# ADC_CPU.net
KiCad netlist of a schematic drawn in Altium Designer
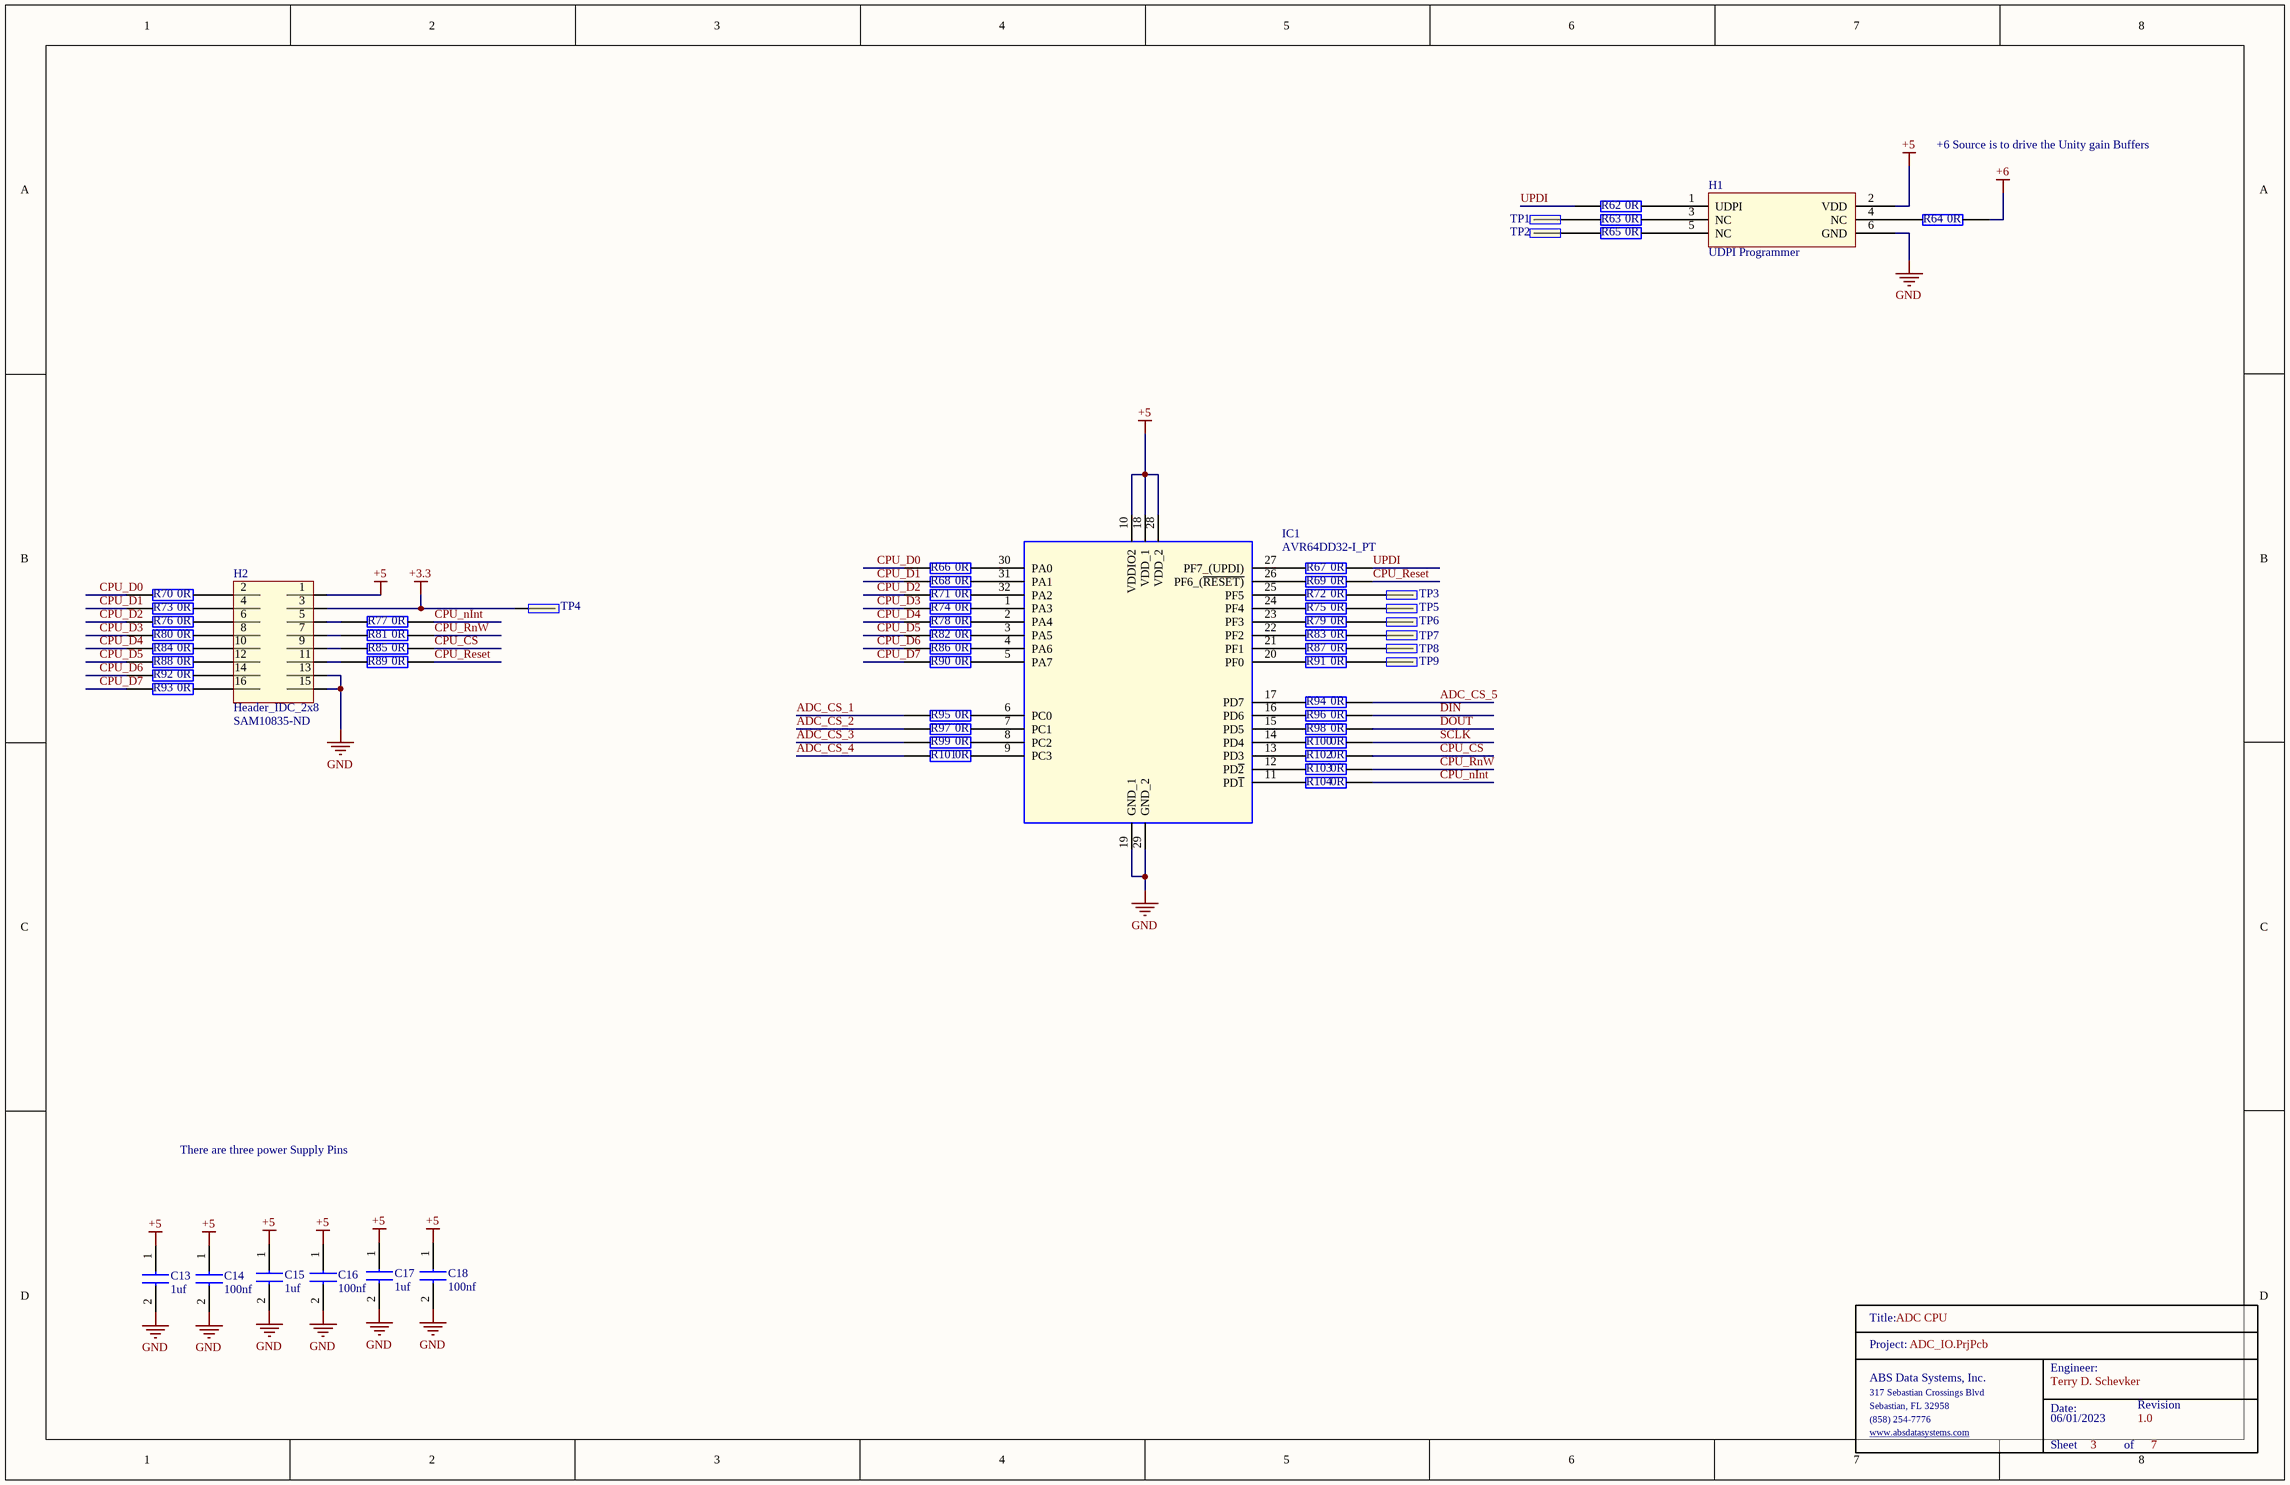
[diagram p0: ADC_CPU.SchDoc]

(export (version "E")
  (design (tool "Eeschema 10.0.6"))
  (components
    (comp (ref "C13")
      (value "1uf")
      (footprint "0603")
      (description "Samsung Electro-Mechanics 0603 1uf")
      (libsource (lib "Capacitors") (part "CL10B105KA8NNNL"))
    )
    (comp (ref "C14")
      (value "100nf")
      (footprint "0603")
      (description "Samsung Electro-Mechanics 0603 100nf")
      (libsource (lib "Capacitors") (part "CL10B104JB8NNNC"))
    )
    (comp (ref "C15")
      (value "1uf")
      (footprint "0603")
      (description "Samsung Electro-Mechanics 0603 1uf")
      (libsource (lib "Capacitors") (part "CL10B105KA8NNNL"))
    )
    (comp (ref "C16")
      (value "100nf")
      (footprint "0603")
      (description "Samsung Electro-Mechanics 0603 100nf")
      (libsource (lib "Capacitors") (part "CL10B104JB8NNNC"))
    )
    (comp (ref "C17")
      (value "1uf")
      (footprint "0603")
      (description "Samsung Electro-Mechanics 0603 1uf")
      (libsource (lib "Capacitors") (part "CL10B105KA8NNNL"))
    )
    (comp (ref "C18")
      (value "100nf")
      (footprint "0603")
      (description "Samsung Electro-Mechanics 0603 100nf")
      (libsource (lib "Capacitors") (part "CL10B104JB8NNNC"))
    )
    (comp (ref "H1")
      (value "UDPI Programmer")
      (footprint "HDR2X3")
      (description "6 Pin 2X3 Through Hole Header")
      (libsource (lib "Misc") (part "UDPI Programmer"))
    )
    (comp (ref "H2")
      (value "Header_IDC_2x8")
      (footprint "HEADER16")
      (description "16 Pin 2x8 Through Hold IDC Connector")
      (fields
        (field (name "MANUFACTURER") "Samtec")
        (field (name "MANUFACTURER PART NUMBER") "TST-108-01-G-D")
        (field (name "SUPPLIER PART NUMBER 1") "SAM10835-ND")
      )
      (libsource (lib "Misc") (part "Header_IDC_2x8"))
    )
    (comp (ref "IC1")
      (value "AVR64DD32-I_PT")
      (footprint "CPU_Memory:QFP80P900X900X120-32N")
      (description "Integrated Circuit")
      (fields (field (name "MANUFACTURER_PART_NUMBER") "AVR64DD32-I/PT ¦ MULTI-VOLTAGE I/O"))
      (libsource (lib "CPU_Memory") (part "AVR64DD32-I_PT"))
    )
    (comp (ref "R62")
      (value "0R")
      (footprint "0603")
      (description "YAGEO 0603 0 ohm")
      (fields
        (field (name "MOUSER PART NUMBER") "603-RC0603JR-070RL")
        (field (name "MANUFACTURER_PART_NUMBER") "RC0603JR-070RL")
      )
      (libsource (lib "Resistors") (part "RC0603JR-070RL"))
    )
    (comp (ref "R63")
      (value "0R")
      (footprint "0603")
      (description "YAGEO 0603 0 ohm")
      (fields
        (field (name "MOUSER PART NUMBER") "603-RC0603JR-070RL")
        (field (name "MANUFACTURER_PART_NUMBER") "RC0603JR-070RL")
      )
      (libsource (lib "Resistors") (part "RC0603JR-070RL"))
    )
    (comp (ref "R64")
      (value "0R")
      (footprint "0603")
      (description "YAGEO 0603 0 ohm")
      (fields
        (field (name "MOUSER PART NUMBER") "603-RC0603JR-070RL")
        (field (name "MANUFACTURER_PART_NUMBER") "RC0603JR-070RL")
      )
      (libsource (lib "Resistors") (part "RC0603JR-070RL"))
    )
    (comp (ref "R65")
      (value "0R")
      (footprint "0603")
      (description "YAGEO 0603 0 ohm")
      (fields
        (field (name "MOUSER PART NUMBER") "603-RC0603JR-070RL")
        (field (name "MANUFACTURER_PART_NUMBER") "RC0603JR-070RL")
      )
      (libsource (lib "Resistors") (part "RC0603JR-070RL"))
    )
    (comp (ref "R66")
      (value "0R")
      (footprint "0603")
      (description "YAGEO 0603 0 ohm")
      (fields
        (field (name "MOUSER PART NUMBER") "603-RC0603JR-070RL")
        (field (name "MANUFACTURER_PART_NUMBER") "RC0603JR-070RL")
      )
      (libsource (lib "Resistors") (part "RC0603JR-070RL"))
    )
    (comp (ref "R67")
      (value "0R")
      (footprint "0603")
      (description "YAGEO 0603 0 ohm")
      (fields
        (field (name "MOUSER PART NUMBER") "603-RC0603JR-070RL")
        (field (name "MANUFACTURER_PART_NUMBER") "RC0603JR-070RL")
      )
      (libsource (lib "Resistors") (part "RC0603JR-070RL"))
    )
    (comp (ref "R68")
      (value "0R")
      (footprint "0603")
      (description "YAGEO 0603 0 ohm")
      (fields
        (field (name "MOUSER PART NUMBER") "603-RC0603JR-070RL")
        (field (name "MANUFACTURER_PART_NUMBER") "RC0603JR-070RL")
      )
      (libsource (lib "Resistors") (part "RC0603JR-070RL"))
    )
    (comp (ref "R69")
      (value "0R")
      (footprint "0603")
      (description "YAGEO 0603 0 ohm")
      (fields
        (field (name "MOUSER PART NUMBER") "603-RC0603JR-070RL")
        (field (name "MANUFACTURER_PART_NUMBER") "RC0603JR-070RL")
      )
      (libsource (lib "Resistors") (part "RC0603JR-070RL"))
    )
    (comp (ref "R70")
      (value "0R")
      (footprint "0603")
      (description "YAGEO 0603 0 ohm")
      (fields
        (field (name "MOUSER PART NUMBER") "603-RC0603JR-070RL")
        (field (name "MANUFACTURER_PART_NUMBER") "RC0603JR-070RL")
      )
      (libsource (lib "Resistors") (part "RC0603JR-070RL"))
    )
    (comp (ref "R71")
      (value "0R")
      (footprint "0603")
      (description "YAGEO 0603 0 ohm")
      (fields
        (field (name "MOUSER PART NUMBER") "603-RC0603JR-070RL")
        (field (name "MANUFACTURER_PART_NUMBER") "RC0603JR-070RL")
      )
      (libsource (lib "Resistors") (part "RC0603JR-070RL"))
    )
    (comp (ref "R72")
      (value "0R")
      (footprint "0603")
      (description "YAGEO 0603 0 ohm")
      (fields
        (field (name "MOUSER PART NUMBER") "603-RC0603JR-070RL")
        (field (name "MANUFACTURER_PART_NUMBER") "RC0603JR-070RL")
      )
      (libsource (lib "Resistors") (part "RC0603JR-070RL"))
    )
    (comp (ref "R73")
      (value "0R")
      (footprint "0603")
      (description "YAGEO 0603 0 ohm")
      (fields
        (field (name "MOUSER PART NUMBER") "603-RC0603JR-070RL")
        (field (name "MANUFACTURER_PART_NUMBER") "RC0603JR-070RL")
      )
      (libsource (lib "Resistors") (part "RC0603JR-070RL"))
    )
    (comp (ref "R74")
      (value "0R")
      (footprint "0603")
      (description "YAGEO 0603 0 ohm")
      (fields
        (field (name "MOUSER PART NUMBER") "603-RC0603JR-070RL")
        (field (name "MANUFACTURER_PART_NUMBER") "RC0603JR-070RL")
      )
      (libsource (lib "Resistors") (part "RC0603JR-070RL"))
    )
    (comp (ref "R75")
      (value "0R")
      (footprint "0603")
      (description "YAGEO 0603 0 ohm")
      (fields
        (field (name "MOUSER PART NUMBER") "603-RC0603JR-070RL")
        (field (name "MANUFACTURER_PART_NUMBER") "RC0603JR-070RL")
      )
      (libsource (lib "Resistors") (part "RC0603JR-070RL"))
    )
    (comp (ref "R76")
      (value "0R")
      (footprint "0603")
      (description "YAGEO 0603 0 ohm")
      (fields
        (field (name "MOUSER PART NUMBER") "603-RC0603JR-070RL")
        (field (name "MANUFACTURER_PART_NUMBER") "RC0603JR-070RL")
      )
      (libsource (lib "Resistors") (part "RC0603JR-070RL"))
    )
    (comp (ref "R77")
      (value "0R")
      (footprint "0603")
      (description "YAGEO 0603 0 ohm")
      (fields
        (field (name "MOUSER PART NUMBER") "603-RC0603JR-070RL")
        (field (name "MANUFACTURER_PART_NUMBER") "RC0603JR-070RL")
      )
      (libsource (lib "Resistors") (part "RC0603JR-070RL"))
    )
    (comp (ref "R78")
      (value "0R")
      (footprint "0603")
      (description "YAGEO 0603 0 ohm")
      (fields
        (field (name "MOUSER PART NUMBER") "603-RC0603JR-070RL")
        (field (name "MANUFACTURER_PART_NUMBER") "RC0603JR-070RL")
      )
      (libsource (lib "Resistors") (part "RC0603JR-070RL"))
    )
    (comp (ref "R79")
      (value "0R")
      (footprint "0603")
      (description "YAGEO 0603 0 ohm")
      (fields
        (field (name "MOUSER PART NUMBER") "603-RC0603JR-070RL")
        (field (name "MANUFACTURER_PART_NUMBER") "RC0603JR-070RL")
      )
      (libsource (lib "Resistors") (part "RC0603JR-070RL"))
    )
    (comp (ref "R80")
      (value "0R")
      (footprint "0603")
      (description "YAGEO 0603 0 ohm")
      (fields
        (field (name "MOUSER PART NUMBER") "603-RC0603JR-070RL")
        (field (name "MANUFACTURER_PART_NUMBER") "RC0603JR-070RL")
      )
      (libsource (lib "Resistors") (part "RC0603JR-070RL"))
    )
    (comp (ref "R81")
      (value "0R")
      (footprint "0603")
      (description "YAGEO 0603 0 ohm")
      (fields
        (field (name "MOUSER PART NUMBER") "603-RC0603JR-070RL")
        (field (name "MANUFACTURER_PART_NUMBER") "RC0603JR-070RL")
      )
      (libsource (lib "Resistors") (part "RC0603JR-070RL"))
    )
    (comp (ref "R82")
      (value "0R")
      (footprint "0603")
      (description "YAGEO 0603 0 ohm")
      (fields
        (field (name "MOUSER PART NUMBER") "603-RC0603JR-070RL")
        (field (name "MANUFACTURER_PART_NUMBER") "RC0603JR-070RL")
      )
      (libsource (lib "Resistors") (part "RC0603JR-070RL"))
    )
    (comp (ref "R83")
      (value "0R")
      (footprint "0603")
      (description "YAGEO 0603 0 ohm")
      (fields
        (field (name "MOUSER PART NUMBER") "603-RC0603JR-070RL")
        (field (name "MANUFACTURER_PART_NUMBER") "RC0603JR-070RL")
      )
      (libsource (lib "Resistors") (part "RC0603JR-070RL"))
    )
    (comp (ref "R84")
      (value "0R")
      (footprint "0603")
      (description "YAGEO 0603 0 ohm")
      (fields
        (field (name "MOUSER PART NUMBER") "603-RC0603JR-070RL")
        (field (name "MANUFACTURER_PART_NUMBER") "RC0603JR-070RL")
      )
      (libsource (lib "Resistors") (part "RC0603JR-070RL"))
    )
    (comp (ref "R85")
      (value "0R")
      (footprint "0603")
      (description "YAGEO 0603 0 ohm")
      (fields
        (field (name "MOUSER PART NUMBER") "603-RC0603JR-070RL")
        (field (name "MANUFACTURER_PART_NUMBER") "RC0603JR-070RL")
      )
      (libsource (lib "Resistors") (part "RC0603JR-070RL"))
    )
    (comp (ref "R86")
      (value "0R")
      (footprint "0603")
      (description "YAGEO 0603 0 ohm")
      (fields
        (field (name "MOUSER PART NUMBER") "603-RC0603JR-070RL")
        (field (name "MANUFACTURER_PART_NUMBER") "RC0603JR-070RL")
      )
      (libsource (lib "Resistors") (part "RC0603JR-070RL"))
    )
    (comp (ref "R87")
      (value "0R")
      (footprint "0603")
      (description "YAGEO 0603 0 ohm")
      (fields
        (field (name "MOUSER PART NUMBER") "603-RC0603JR-070RL")
        (field (name "MANUFACTURER_PART_NUMBER") "RC0603JR-070RL")
      )
      (libsource (lib "Resistors") (part "RC0603JR-070RL"))
    )
    (comp (ref "R88")
      (value "0R")
      (footprint "0603")
      (description "YAGEO 0603 0 ohm")
      (fields
        (field (name "MOUSER PART NUMBER") "603-RC0603JR-070RL")
        (field (name "MANUFACTURER_PART_NUMBER") "RC0603JR-070RL")
      )
      (libsource (lib "Resistors") (part "RC0603JR-070RL"))
    )
    (comp (ref "R89")
      (value "0R")
      (footprint "0603")
      (description "YAGEO 0603 0 ohm")
      (fields
        (field (name "MOUSER PART NUMBER") "603-RC0603JR-070RL")
        (field (name "MANUFACTURER_PART_NUMBER") "RC0603JR-070RL")
      )
      (libsource (lib "Resistors") (part "RC0603JR-070RL"))
    )
    (comp (ref "R90")
      (value "0R")
      (footprint "0603")
      (description "YAGEO 0603 0 ohm")
      (fields
        (field (name "MOUSER PART NUMBER") "603-RC0603JR-070RL")
        (field (name "MANUFACTURER_PART_NUMBER") "RC0603JR-070RL")
      )
      (libsource (lib "Resistors") (part "RC0603JR-070RL"))
    )
    (comp (ref "R91")
      (value "0R")
      (footprint "0603")
      (description "YAGEO 0603 0 ohm")
      (fields
        (field (name "MOUSER PART NUMBER") "603-RC0603JR-070RL")
        (field (name "MANUFACTURER_PART_NUMBER") "RC0603JR-070RL")
      )
      (libsource (lib "Resistors") (part "RC0603JR-070RL"))
    )
    (comp (ref "R92")
      (value "0R")
      (footprint "0603")
      (description "YAGEO 0603 0 ohm")
      (fields
        (field (name "MOUSER PART NUMBER") "603-RC0603JR-070RL")
        (field (name "MANUFACTURER_PART_NUMBER") "RC0603JR-070RL")
      )
      (libsource (lib "Resistors") (part "RC0603JR-070RL"))
    )
    (comp (ref "R93")
      (value "0R")
      (footprint "0603")
      (description "YAGEO 0603 0 ohm")
      (fields
        (field (name "MOUSER PART NUMBER") "603-RC0603JR-070RL")
        (field (name "MANUFACTURER_PART_NUMBER") "RC0603JR-070RL")
      )
      (libsource (lib "Resistors") (part "RC0603JR-070RL"))
    )
    (comp (ref "R94")
      (value "0R")
      (footprint "0603")
      (description "YAGEO 0603 0 ohm")
      (fields
        (field (name "MOUSER PART NUMBER") "603-RC0603JR-070RL")
        (field (name "MANUFACTURER_PART_NUMBER") "RC0603JR-070RL")
      )
      (libsource (lib "Resistors") (part "RC0603JR-070RL"))
    )
    (comp (ref "R95")
      (value "0R")
      (footprint "0603")
      (description "YAGEO 0603 0 ohm")
      (fields
        (field (name "MOUSER PART NUMBER") "603-RC0603JR-070RL")
        (field (name "MANUFACTURER_PART_NUMBER") "RC0603JR-070RL")
      )
      (libsource (lib "Resistors") (part "RC0603JR-070RL"))
    )
    (comp (ref "R96")
      (value "0R")
      (footprint "0603")
      (description "YAGEO 0603 0 ohm")
      (fields
        (field (name "MOUSER PART NUMBER") "603-RC0603JR-070RL")
        (field (name "MANUFACTURER_PART_NUMBER") "RC0603JR-070RL")
      )
      (libsource (lib "Resistors") (part "RC0603JR-070RL"))
    )
    (comp (ref "R97")
      (value "0R")
      (footprint "0603")
      (description "YAGEO 0603 0 ohm")
      (fields
        (field (name "MOUSER PART NUMBER") "603-RC0603JR-070RL")
        (field (name "MANUFACTURER_PART_NUMBER") "RC0603JR-070RL")
      )
      (libsource (lib "Resistors") (part "RC0603JR-070RL"))
    )
    (comp (ref "R98")
      (value "0R")
      (footprint "0603")
      (description "YAGEO 0603 0 ohm")
      (fields
        (field (name "MOUSER PART NUMBER") "603-RC0603JR-070RL")
        (field (name "MANUFACTURER_PART_NUMBER") "RC0603JR-070RL")
      )
      (libsource (lib "Resistors") (part "RC0603JR-070RL"))
    )
    (comp (ref "R99")
      (value "0R")
      (footprint "0603")
      (description "YAGEO 0603 0 ohm")
      (fields
        (field (name "MOUSER PART NUMBER") "603-RC0603JR-070RL")
        (field (name "MANUFACTURER_PART_NUMBER") "RC0603JR-070RL")
      )
      (libsource (lib "Resistors") (part "RC0603JR-070RL"))
    )
    (comp (ref "R100")
      (value "0R")
      (footprint "0603")
      (description "YAGEO 0603 0 ohm")
      (fields
        (field (name "MOUSER PART NUMBER") "603-RC0603JR-070RL")
        (field (name "MANUFACTURER_PART_NUMBER") "RC0603JR-070RL")
      )
      (libsource (lib "Resistors") (part "RC0603JR-070RL"))
    )
    (comp (ref "R101")
      (value "0R")
      (footprint "0603")
      (description "YAGEO 0603 0 ohm")
      (fields
        (field (name "MOUSER PART NUMBER") "603-RC0603JR-070RL")
        (field (name "MANUFACTURER_PART_NUMBER") "RC0603JR-070RL")
      )
      (libsource (lib "Resistors") (part "RC0603JR-070RL"))
    )
    (comp (ref "R102")
      (value "0R")
      (footprint "0603")
      (description "YAGEO 0603 0 ohm")
      (fields
        (field (name "MOUSER PART NUMBER") "603-RC0603JR-070RL")
        (field (name "MANUFACTURER_PART_NUMBER") "RC0603JR-070RL")
      )
      (libsource (lib "Resistors") (part "RC0603JR-070RL"))
    )
    (comp (ref "R103")
      (value "0R")
      (footprint "0603")
      (description "YAGEO 0603 0 ohm")
      (fields
        (field (name "MOUSER PART NUMBER") "603-RC0603JR-070RL")
        (field (name "MANUFACTURER_PART_NUMBER") "RC0603JR-070RL")
      )
      (libsource (lib "Resistors") (part "RC0603JR-070RL"))
    )
    (comp (ref "R104")
      (value "0R")
      (footprint "0603")
      (description "YAGEO 0603 0 ohm")
      (fields
        (field (name "MOUSER PART NUMBER") "603-RC0603JR-070RL")
        (field (name "MANUFACTURER_PART_NUMBER") "RC0603JR-070RL")
      )
      (libsource (lib "Resistors") (part "RC0603JR-070RL"))
    )
    (comp (ref "TitleBlock_3") (value "TitleBlock") (libsource (lib "Misc") (part "TitleBlock")))
    (comp (ref "TP1")
      (value "TP")
      (footprint "TP")
      (fields
        (field (name "MANUFACTURER") "Samtec")
        (field (name "MANUFACTURER PART NUMBER") "TST-105-01-G-D")
      )
      (libsource (lib "") (part "TP_1"))
    )
    (comp (ref "TP2")
      (value "TP")
      (footprint "TP")
      (fields
        (field (name "MANUFACTURER") "Samtec")
        (field (name "MANUFACTURER PART NUMBER") "TST-105-01-G-D")
      )
      (libsource (lib "") (part "TP_1"))
    )
    (comp (ref "TP3")
      (value "TP")
      (footprint "TP")
      (fields
        (field (name "MANUFACTURER") "Samtec")
        (field (name "MANUFACTURER PART NUMBER") "TST-105-01-G-D")
      )
      (libsource (lib "Misc") (part "TP"))
    )
    (comp (ref "TP4")
      (value "TP")
      (footprint "TP")
      (fields
        (field (name "MANUFACTURER") "Samtec")
        (field (name "MANUFACTURER PART NUMBER") "TST-105-01-G-D")
      )
      (libsource (lib "Misc") (part "TP"))
    )
    (comp (ref "TP5")
      (value "TP")
      (footprint "TP")
      (fields
        (field (name "MANUFACTURER") "Samtec")
        (field (name "MANUFACTURER PART NUMBER") "TST-105-01-G-D")
      )
      (libsource (lib "Misc") (part "TP"))
    )
    (comp (ref "TP6")
      (value "TP")
      (footprint "TP")
      (fields
        (field (name "MANUFACTURER") "Samtec")
        (field (name "MANUFACTURER PART NUMBER") "TST-105-01-G-D")
      )
      (libsource (lib "Misc") (part "TP"))
    )
    (comp (ref "TP7")
      (value "TP")
      (footprint "TP")
      (fields
        (field (name "MANUFACTURER") "Samtec")
        (field (name "MANUFACTURER PART NUMBER") "TST-105-01-G-D")
      )
      (libsource (lib "Misc") (part "TP"))
    )
    (comp (ref "TP8")
      (value "TP")
      (footprint "TP")
      (fields
        (field (name "MANUFACTURER") "Samtec")
        (field (name "MANUFACTURER PART NUMBER") "TST-105-01-G-D")
      )
      (libsource (lib "Misc") (part "TP"))
    )
    (comp (ref "TP9")
      (value "TP")
      (footprint "TP")
      (fields
        (field (name "MANUFACTURER") "Samtec")
        (field (name "MANUFACTURER PART NUMBER") "TST-105-01-G-D")
      )
      (libsource (lib "Misc") (part "TP"))
    )
  )
  (nets
    (net (code "1") (name "+3.3") (class "Default")
      (node (ref "H2") (pin "3") (pinfunction "3_3") (pintype "passive"))
      (node (ref "TP4") (pin "1") (pinfunction "1_1") (pintype "passive"))
    )
    (net (code "2") (name "+5") (class "Default")
      (node (ref "C13") (pin "1") (pinfunction "1_1") (pintype "passive"))
      (node (ref "C14") (pin "1") (pinfunction "1_1") (pintype "passive"))
      (node (ref "C15") (pin "1") (pinfunction "1_1") (pintype "passive"))
      (node (ref "C16") (pin "1") (pinfunction "1_1") (pintype "passive"))
      (node (ref "C17") (pin "1") (pinfunction "1_1") (pintype "passive"))
      (node (ref "C18") (pin "1") (pinfunction "1_1") (pintype "passive"))
      (node (ref "H1") (pin "2") (pinfunction "VDD_2") (pintype "passive"))
      (node (ref "H2") (pin "1") (pinfunction "1_1") (pintype "passive"))
      (node (ref "IC1") (pin "10") (pinfunction "VDDIO2_10") (pintype "passive"))
      (node (ref "IC1") (pin "18") (pinfunction "VDD_1_18") (pintype "passive"))
      (node (ref "IC1") (pin "28") (pinfunction "VDD_2_28") (pintype "passive"))
    )
    (net (code "3") (name "+6") (class "Default")
      (node (ref "R64") (pin "2") (pinfunction "2_2") (pintype "passive"))
    )
    (net (code "4") (name "/ADC_CS_1") (class "Default")
      (node (ref "R95") (pin "1") (pinfunction "1_1") (pintype "passive"))
    )
    (net (code "5") (name "/ADC_CS_2") (class "Default")
      (node (ref "R97") (pin "1") (pinfunction "1_1") (pintype "passive"))
    )
    (net (code "6") (name "/ADC_CS_3") (class "Default")
      (node (ref "R99") (pin "1") (pinfunction "1_1") (pintype "passive"))
    )
    (net (code "7") (name "/ADC_CS_4") (class "Default")
      (node (ref "R101") (pin "1") (pinfunction "1_1") (pintype "passive"))
    )
    (net (code "8") (name "/ADC_CS_5") (class "Default")
      (node (ref "R94") (pin "2") (pinfunction "2_2") (pintype "passive"))
    )
    (net (code "9") (name "/CPU_CS") (class "Default")
      (node (ref "R102") (pin "2") (pinfunction "2_2") (pintype "passive"))
      (node (ref "R85") (pin "2") (pinfunction "2_2") (pintype "passive"))
    )
    (net (code "10") (name "/CPU_D0") (class "Default")
      (node (ref "R66") (pin "1") (pinfunction "1_1") (pintype "passive"))
      (node (ref "R70") (pin "1") (pinfunction "1_1") (pintype "passive"))
    )
    (net (code "11") (name "/CPU_D1") (class "Default")
      (node (ref "R68") (pin "1") (pinfunction "1_1") (pintype "passive"))
      (node (ref "R73") (pin "1") (pinfunction "1_1") (pintype "passive"))
    )
    (net (code "12") (name "/CPU_D2") (class "Default")
      (node (ref "R71") (pin "1") (pinfunction "1_1") (pintype "passive"))
      (node (ref "R76") (pin "1") (pinfunction "1_1") (pintype "passive"))
    )
    (net (code "13") (name "/CPU_D3") (class "Default")
      (node (ref "R74") (pin "1") (pinfunction "1_1") (pintype "passive"))
      (node (ref "R80") (pin "1") (pinfunction "1_1") (pintype "passive"))
    )
    (net (code "14") (name "/CPU_D4") (class "Default")
      (node (ref "R78") (pin "1") (pinfunction "1_1") (pintype "passive"))
      (node (ref "R84") (pin "1") (pinfunction "1_1") (pintype "passive"))
    )
    (net (code "15") (name "/CPU_D5") (class "Default")
      (node (ref "R82") (pin "1") (pinfunction "1_1") (pintype "passive"))
      (node (ref "R88") (pin "1") (pinfunction "1_1") (pintype "passive"))
    )
    (net (code "16") (name "/CPU_D6") (class "Default")
      (node (ref "R86") (pin "1") (pinfunction "1_1") (pintype "passive"))
      (node (ref "R92") (pin "1") (pinfunction "1_1") (pintype "passive"))
    )
    (net (code "17") (name "/CPU_D7") (class "Default")
      (node (ref "R90") (pin "1") (pinfunction "1_1") (pintype "passive"))
      (node (ref "R93") (pin "1") (pinfunction "1_1") (pintype "passive"))
    )
    (net (code "18") (name "/CPU_Reset") (class "Default")
      (node (ref "R69") (pin "2") (pinfunction "2_2") (pintype "passive"))
      (node (ref "R89") (pin "2") (pinfunction "2_2") (pintype "passive"))
    )
    (net (code "19") (name "/CPU_RnW") (class "Default")
      (node (ref "R103") (pin "2") (pinfunction "2_2") (pintype "passive"))
      (node (ref "R81") (pin "2") (pinfunction "2_2") (pintype "passive"))
    )
    (net (code "20") (name "/CPU_nInt") (class "Default")
      (node (ref "R104") (pin "2") (pinfunction "2_2") (pintype "passive"))
      (node (ref "R77") (pin "2") (pinfunction "2_2") (pintype "passive"))
    )
    (net (code "21") (name "/DIN") (class "Default")
      (node (ref "R96") (pin "2") (pinfunction "2_2") (pintype "passive"))
    )
    (net (code "22") (name "/DOUT") (class "Default")
      (node (ref "R98") (pin "2") (pinfunction "2_2") (pintype "passive"))
    )
    (net (code "23") (name "/SCLK") (class "Default")
      (node (ref "R100") (pin "2") (pinfunction "2_2") (pintype "passive"))
    )
    (net (code "24") (name "/UPDI") (class "Default")
      (node (ref "R62") (pin "1") (pinfunction "1_1") (pintype "passive"))
      (node (ref "R67") (pin "2") (pinfunction "2_2") (pintype "passive"))
    )
    (net (code "25") (name "GND") (class "Default")
      (node (ref "C13") (pin "2") (pinfunction "2_2") (pintype "passive"))
      (node (ref "C14") (pin "2") (pinfunction "2_2") (pintype "passive"))
      (node (ref "C15") (pin "2") (pinfunction "2_2") (pintype "passive"))
      (node (ref "C16") (pin "2") (pinfunction "2_2") (pintype "passive"))
      (node (ref "C17") (pin "2") (pinfunction "2_2") (pintype "passive"))
      (node (ref "C18") (pin "2") (pinfunction "2_2") (pintype "passive"))
      (node (ref "H1") (pin "6") (pinfunction "GND_6") (pintype "passive"))
      (node (ref "H2") (pin "13") (pinfunction "13_13") (pintype "passive"))
      (node (ref "H2") (pin "15") (pinfunction "15_15") (pintype "passive"))
      (node (ref "IC1") (pin "19") (pinfunction "GND_1_19") (pintype "passive"))
      (node (ref "IC1") (pin "29") (pinfunction "GND_2_29") (pintype "passive"))
    )
    (net (code "26") (name "Net-(H1-NC-Pad3)") (class "Default")
      (node (ref "H1") (pin "3") (pinfunction "NC_3") (pintype "passive"))
      (node (ref "R63") (pin "2") (pinfunction "2_2") (pintype "passive"))
    )
    (net (code "27") (name "Net-(H1-NC-Pad4)") (class "Default")
      (node (ref "H1") (pin "4") (pinfunction "NC_4") (pintype "passive"))
      (node (ref "R64") (pin "1") (pinfunction "1_1") (pintype "passive"))
    )
    (net (code "28") (name "Net-(H1-NC-Pad5)") (class "Default")
      (node (ref "H1") (pin "5") (pinfunction "NC_5") (pintype "passive"))
      (node (ref "R65") (pin "2") (pinfunction "2_2") (pintype "passive"))
    )
    (net (code "29") (name "Net-(H1-UDPI)") (class "Default")
      (node (ref "H1") (pin "1") (pinfunction "UDPI_1") (pintype "passive"))
      (node (ref "R62") (pin "2") (pinfunction "2_2") (pintype "passive"))
    )
    (net (code "30") (name "Net-(H2-Pad2)") (class "Default")
      (node (ref "H2") (pin "2") (pinfunction "2_2") (pintype "passive"))
      (node (ref "R70") (pin "2") (pinfunction "2_2") (pintype "passive"))
    )
    (net (code "31") (name "Net-(H2-Pad4)") (class "Default")
      (node (ref "H2") (pin "4") (pinfunction "4_4") (pintype "passive"))
      (node (ref "R73") (pin "2") (pinfunction "2_2") (pintype "passive"))
    )
    (net (code "32") (name "Net-(H2-Pad5)") (class "Default")
      (node (ref "H2") (pin "5") (pinfunction "5_5") (pintype "passive"))
      (node (ref "R77") (pin "1") (pinfunction "1_1") (pintype "passive"))
    )
    (net (code "33") (name "Net-(H2-Pad6)") (class "Default")
      (node (ref "H2") (pin "6") (pinfunction "6_6") (pintype "passive"))
      (node (ref "R76") (pin "2") (pinfunction "2_2") (pintype "passive"))
    )
    (net (code "34") (name "Net-(H2-Pad7)") (class "Default")
      (node (ref "H2") (pin "7") (pinfunction "7_7") (pintype "passive"))
      (node (ref "R81") (pin "1") (pinfunction "1_1") (pintype "passive"))
    )
    (net (code "35") (name "Net-(H2-Pad8)") (class "Default")
      (node (ref "H2") (pin "8") (pinfunction "8_8") (pintype "passive"))
      (node (ref "R80") (pin "2") (pinfunction "2_2") (pintype "passive"))
    )
    (net (code "36") (name "Net-(H2-Pad9)") (class "Default")
      (node (ref "H2") (pin "9") (pinfunction "9_9") (pintype "passive"))
      (node (ref "R85") (pin "1") (pinfunction "1_1") (pintype "passive"))
    )
    (net (code "37") (name "Net-(H2-Pad10)") (class "Default")
      (node (ref "H2") (pin "10") (pinfunction "10_10") (pintype "passive"))
      (node (ref "R84") (pin "2") (pinfunction "2_2") (pintype "passive"))
    )
    (net (code "38") (name "Net-(H2-Pad11)") (class "Default")
      (node (ref "H2") (pin "11") (pinfunction "11_11") (pintype "passive"))
      (node (ref "R89") (pin "1") (pinfunction "1_1") (pintype "passive"))
    )
    (net (code "39") (name "Net-(H2-Pad12)") (class "Default")
      (node (ref "H2") (pin "12") (pinfunction "12_12") (pintype "passive"))
      (node (ref "R88") (pin "2") (pinfunction "2_2") (pintype "passive"))
    )
    (net (code "40") (name "Net-(H2-Pad14)") (class "Default")
      (node (ref "H2") (pin "14") (pinfunction "14_14") (pintype "passive"))
      (node (ref "R92") (pin "2") (pinfunction "2_2") (pintype "passive"))
    )
    (net (code "41") (name "Net-(H2-Pad16)") (class "Default")
      (node (ref "H2") (pin "16") (pinfunction "16_16") (pintype "passive"))
      (node (ref "R93") (pin "2") (pinfunction "2_2") (pintype "passive"))
    )
    (net (code "42") (name "Net-(IC1-PA0)") (class "Default")
      (node (ref "IC1") (pin "30") (pinfunction "PA0_30") (pintype "passive"))
      (node (ref "R66") (pin "2") (pinfunction "2_2") (pintype "passive"))
    )
    (net (code "43") (name "Net-(IC1-PA1)") (class "Default")
      (node (ref "IC1") (pin "31") (pinfunction "PA1_31") (pintype "passive"))
      (node (ref "R68") (pin "2") (pinfunction "2_2") (pintype "passive"))
    )
    (net (code "44") (name "Net-(IC1-PA2)") (class "Default")
      (node (ref "IC1") (pin "32") (pinfunction "PA2_32") (pintype "passive"))
      (node (ref "R71") (pin "2") (pinfunction "2_2") (pintype "passive"))
    )
    (net (code "45") (name "Net-(IC1-PA3)") (class "Default")
      (node (ref "IC1") (pin "1") (pinfunction "PA3_1") (pintype "passive"))
      (node (ref "R74") (pin "2") (pinfunction "2_2") (pintype "passive"))
    )
    (net (code "46") (name "Net-(IC1-PA4)") (class "Default")
      (node (ref "IC1") (pin "2") (pinfunction "PA4_2") (pintype "passive"))
      (node (ref "R78") (pin "2") (pinfunction "2_2") (pintype "passive"))
    )
    (net (code "47") (name "Net-(IC1-PA5)") (class "Default")
      (node (ref "IC1") (pin "3") (pinfunction "PA5_3") (pintype "passive"))
      (node (ref "R82") (pin "2") (pinfunction "2_2") (pintype "passive"))
    )
    (net (code "48") (name "Net-(IC1-PA6)") (class "Default")
      (node (ref "IC1") (pin "4") (pinfunction "PA6_4") (pintype "passive"))
      (node (ref "R86") (pin "2") (pinfunction "2_2") (pintype "passive"))
    )
    (net (code "49") (name "Net-(IC1-PA7)") (class "Default")
      (node (ref "IC1") (pin "5") (pinfunction "PA7_5") (pintype "passive"))
      (node (ref "R90") (pin "2") (pinfunction "2_2") (pintype "passive"))
    )
    (net (code "50") (name "Net-(IC1-PC0)") (class "Default")
      (node (ref "IC1") (pin "6") (pinfunction "PC0_6") (pintype "passive"))
      (node (ref "R95") (pin "2") (pinfunction "2_2") (pintype "passive"))
    )
    (net (code "51") (name "Net-(IC1-PC1)") (class "Default")
      (node (ref "IC1") (pin "7") (pinfunction "PC1_7") (pintype "passive"))
      (node (ref "R97") (pin "2") (pinfunction "2_2") (pintype "passive"))
    )
    (net (code "52") (name "Net-(IC1-PC2)") (class "Default")
      (node (ref "IC1") (pin "8") (pinfunction "PC2_8") (pintype "passive"))
      (node (ref "R99") (pin "2") (pinfunction "2_2") (pintype "passive"))
    )
    (net (code "53") (name "Net-(IC1-PC3)") (class "Default")
      (node (ref "IC1") (pin "9") (pinfunction "PC3_9") (pintype "passive"))
      (node (ref "R101") (pin "2") (pinfunction "2_2") (pintype "passive"))
    )
    (net (code "54") (name "Net-(IC1-PD3)") (class "Default")
      (node (ref "IC1") (pin "13") (pinfunction "PD3_13") (pintype "passive"))
      (node (ref "R102") (pin "1") (pinfunction "1_1") (pintype "passive"))
    )
    (net (code "55") (name "Net-(IC1-PD4)") (class "Default")
      (node (ref "IC1") (pin "14") (pinfunction "PD4_14") (pintype "passive"))
      (node (ref "R100") (pin "1") (pinfunction "1_1") (pintype "passive"))
    )
    (net (code "56") (name "Net-(IC1-PD5)") (class "Default")
      (node (ref "IC1") (pin "15") (pinfunction "PD5_15") (pintype "passive"))
      (node (ref "R98") (pin "1") (pinfunction "1_1") (pintype "passive"))
    )
    (net (code "57") (name "Net-(IC1-PD6)") (class "Default")
      (node (ref "IC1") (pin "16") (pinfunction "PD6_16") (pintype "passive"))
      (node (ref "R96") (pin "1") (pinfunction "1_1") (pintype "passive"))
    )
    (net (code "58") (name "Net-(IC1-PD7)") (class "Default")
      (node (ref "IC1") (pin "17") (pinfunction "PD7_17") (pintype "passive"))
      (node (ref "R94") (pin "1") (pinfunction "1_1") (pintype "passive"))
    )
    (net (code "59") (name "Net-(IC1-PD~{1})") (class "Default")
      (node (ref "IC1") (pin "11") (pinfunction "PD~{1}_11") (pintype "passive"))
      (node (ref "R104") (pin "1") (pinfunction "1_1") (pintype "passive"))
    )
    (net (code "60") (name "Net-(IC1-PD~{2})") (class "Default")
      (node (ref "IC1") (pin "12") (pinfunction "PD~{2}_12") (pintype "passive"))
      (node (ref "R103") (pin "1") (pinfunction "1_1") (pintype "passive"))
    )
    (net (code "61") (name "Net-(IC1-PF0)") (class "Default")
      (node (ref "IC1") (pin "20") (pinfunction "PF0_20") (pintype "passive"))
      (node (ref "R91") (pin "1") (pinfunction "1_1") (pintype "passive"))
    )
    (net (code "62") (name "Net-(IC1-PF1)") (class "Default")
      (node (ref "IC1") (pin "21") (pinfunction "PF1_21") (pintype "passive"))
      (node (ref "R87") (pin "1") (pinfunction "1_1") (pintype "passive"))
    )
    (net (code "63") (name "Net-(IC1-PF2)") (class "Default")
      (node (ref "IC1") (pin "22") (pinfunction "PF2_22") (pintype "passive"))
      (node (ref "R83") (pin "1") (pinfunction "1_1") (pintype "passive"))
    )
    (net (code "64") (name "Net-(IC1-PF3)") (class "Default")
      (node (ref "IC1") (pin "23") (pinfunction "PF3_23") (pintype "passive"))
      (node (ref "R79") (pin "1") (pinfunction "1_1") (pintype "passive"))
    )
    (net (code "65") (name "Net-(IC1-PF4)") (class "Default")
      (node (ref "IC1") (pin "24") (pinfunction "PF4_24") (pintype "passive"))
      (node (ref "R75") (pin "1") (pinfunction "1_1") (pintype "passive"))
    )
    (net (code "66") (name "Net-(IC1-PF5)") (class "Default")
      (node (ref "IC1") (pin "25") (pinfunction "PF5_25") (pintype "passive"))
      (node (ref "R72") (pin "1") (pinfunction "1_1") (pintype "passive"))
    )
    (net (code "67") (name "Net-(IC1-PF6_(~{RESET)})") (class "Default")
      (node (ref "IC1") (pin "26") (pinfunction "PF6_(~{RESET)}_26") (pintype "passive"))
      (node (ref "R69") (pin "1") (pinfunction "1_1") (pintype "passive"))
    )
    (net (code "68") (name "Net-(IC1-PF7_(UPDI))") (class "Default")
      (node (ref "IC1") (pin "27") (pinfunction "PF7_(UPDI)_27") (pintype "passive"))
      (node (ref "R67") (pin "1") (pinfunction "1_1") (pintype "passive"))
    )
    (net (code "69") (name "Net-(R63-Pad1)") (class "Default")
      (node (ref "R63") (pin "1") (pinfunction "1_1") (pintype "passive"))
      (node (ref "TP1") (pin "1") (pinfunction "1_1") (pintype "passive"))
    )
    (net (code "70") (name "Net-(R65-Pad1)") (class "Default")
      (node (ref "R65") (pin "1") (pinfunction "1_1") (pintype "passive"))
      (node (ref "TP2") (pin "1") (pinfunction "1_1") (pintype "passive"))
    )
    (net (code "71") (name "Net-(R72-Pad2)") (class "Default")
      (node (ref "R72") (pin "2") (pinfunction "2_2") (pintype "passive"))
      (node (ref "TP3") (pin "1") (pinfunction "1_1") (pintype "passive"))
    )
    (net (code "72") (name "Net-(R75-Pad2)") (class "Default")
      (node (ref "R75") (pin "2") (pinfunction "2_2") (pintype "passive"))
      (node (ref "TP5") (pin "1") (pinfunction "1_1") (pintype "passive"))
    )
    (net (code "73") (name "Net-(R79-Pad2)") (class "Default")
      (node (ref "R79") (pin "2") (pinfunction "2_2") (pintype "passive"))
      (node (ref "TP6") (pin "1") (pinfunction "1_1") (pintype "passive"))
    )
    (net (code "74") (name "Net-(R83-Pad2)") (class "Default")
      (node (ref "R83") (pin "2") (pinfunction "2_2") (pintype "passive"))
      (node (ref "TP7") (pin "1") (pinfunction "1_1") (pintype "passive"))
    )
    (net (code "75") (name "Net-(R87-Pad2)") (class "Default")
      (node (ref "R87") (pin "2") (pinfunction "2_2") (pintype "passive"))
      (node (ref "TP8") (pin "1") (pinfunction "1_1") (pintype "passive"))
    )
    (net (code "76") (name "Net-(R91-Pad2)") (class "Default")
      (node (ref "R91") (pin "2") (pinfunction "2_2") (pintype "passive"))
      (node (ref "TP9") (pin "1") (pinfunction "1_1") (pintype "passive"))
    )
  )
)
